# mcp9800.net
KiCad netlist of a schematic drawn in Altium Designer
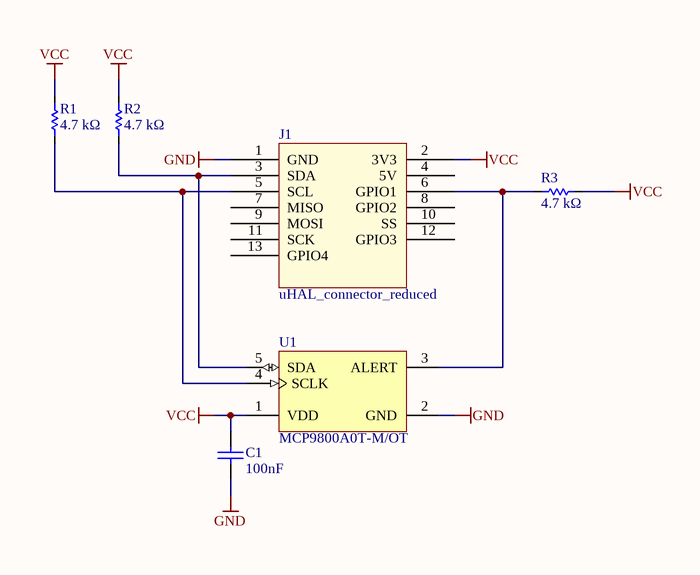
[diagram p0: mcp9800.SchDoc]

(export (version "E")
  (design (tool "Eeschema 10.0.6"))
  (components
    (comp (ref "C1")
      (value "Murata GCM188R71H104KA57D")
      (footprint "CAPC1608X90X35ML10T15")
      (description "CAP CER 0.1UF 50V 10% X7R 0603")
      (fields (field (name "CAPACITANCE") "100nF"))
      (libsource (lib "CommunityVault") (part "CMP-119667-3"))
    )
    (comp (ref "J1")
      (value "uHAL_connector_reduced")
      (footprint "PCB-45ncoppm4oopozvqifsq-1")
      (description "connector for uHAL with reduced pin number")
      (libsource (lib "CommunityVault") (part "CMP-2q23h2cwhjlfm8s6r7i8-1"))
    )
    (comp (ref "R1")
      (value "CRCW06034K70FKEAHP")
      (footprint "PCB-cmzy4aezi5zhn2bew7lt-1")
      (description "Surface Mount Chip Resistor, Thick Film, AEC-Q200 CRCW Series, 4.7 kohm, 250 mW, 1%, 75 V")
      (fields (field (name "RESISTANCE") "4.7 kΩ"))
      (libsource (lib "CommunityVault") (part "CMP-40e08b60e91c9f27-1"))
    )
    (comp (ref "R2")
      (value "CRCW06034K70FKEAHP")
      (footprint "PCB-cmzy4aezi5zhn2bew7lt-1")
      (description "Surface Mount Chip Resistor, Thick Film, AEC-Q200 CRCW Series, 4.7 kohm, 250 mW, 1%, 75 V")
      (fields (field (name "RESISTANCE") "4.7 kΩ"))
      (libsource (lib "CommunityVault") (part "CMP-40e08b60e91c9f27-1"))
    )
    (comp (ref "R3")
      (value "CRCW06034K70FKEAHP")
      (footprint "PCB-cmzy4aezi5zhn2bew7lt-1")
      (description "Surface Mount Chip Resistor, Thick Film, AEC-Q200 CRCW Series, 4.7 kohm, 250 mW, 1%, 75 V")
      (fields (field (name "RESISTANCE") "4.7 kΩ"))
      (libsource (lib "CommunityVault") (part "CMP-40e08b60e91c9f27-1"))
    )
    (comp (ref "U1")
      (value "MCP9800A0T-M/OT")
      (footprint "SOT-23-OT5_L")
      (libsource (lib "CommunityVault") (part "SEN-TEMP-MCP980X-5"))
    )
  )
  (nets
    (net (code "1") (name "GND") (class "Default")
      (node (ref "C1") (pin "1") (pinfunction "1_1") (pintype "passive"))
      (node (ref "J1") (pin "1") (pinfunction "GND_1") (pintype "passive"))
      (node (ref "U1") (pin "2") (pinfunction "GND_2") (pintype "power_in"))
    )
    (net (code "2") (name "Net-(J1-GPIO1)") (class "Default")
      (node (ref "J1") (pin "6") (pinfunction "GPIO1_6") (pintype "passive"))
      (node (ref "R3") (pin "2") (pinfunction "2_2") (pintype "passive"))
      (node (ref "U1") (pin "3") (pinfunction "ALERT_3") (pintype "open_collector"))
    )
    (net (code "3") (name "Net-(J1-SCL)") (class "Default")
      (node (ref "J1") (pin "5") (pinfunction "SCL_5") (pintype "passive"))
      (node (ref "R1") (pin "1") (pinfunction "1_1") (pintype "passive"))
      (node (ref "U1") (pin "4") (pinfunction "SCLK_4") (pintype "input"))
    )
    (net (code "4") (name "Net-(J1-SDA)") (class "Default")
      (node (ref "J1") (pin "3") (pinfunction "SDA_3") (pintype "passive"))
      (node (ref "R2") (pin "1") (pinfunction "1_1") (pintype "passive"))
      (node (ref "U1") (pin "5") (pinfunction "SDA_5") (pintype "bidirectional"))
    )
    (net (code "5") (name "VCC") (class "Default")
      (node (ref "C1") (pin "2") (pinfunction "2_2") (pintype "passive"))
      (node (ref "J1") (pin "2") (pinfunction "3V3_2") (pintype "passive"))
      (node (ref "R1") (pin "2") (pinfunction "2_2") (pintype "passive"))
      (node (ref "R2") (pin "2") (pinfunction "2_2") (pintype "passive"))
      (node (ref "R3") (pin "1") (pinfunction "1_1") (pintype "passive"))
      (node (ref "U1") (pin "1") (pinfunction "VDD_1") (pintype "power_in"))
    )
    (net (code "6") (name "unconnected-(J1-5V-Pad4)") (class "Default")
      (node (ref "J1") (pin "4") (pinfunction "5V_4") (pintype "passive"))
    )
    (net (code "7") (name "unconnected-(J1-GPIO2-Pad8)") (class "Default")
      (node (ref "J1") (pin "8") (pinfunction "GPIO2_8") (pintype "passive"))
    )
    (net (code "8") (name "unconnected-(J1-GPIO3-Pad12)") (class "Default")
      (node (ref "J1") (pin "12") (pinfunction "GPIO3_12") (pintype "passive"))
    )
    (net (code "9") (name "unconnected-(J1-GPIO4-Pad13)") (class "Default")
      (node (ref "J1") (pin "13") (pinfunction "GPIO4_13") (pintype "passive"))
    )
    (net (code "10") (name "unconnected-(J1-MISO-Pad7)") (class "Default")
      (node (ref "J1") (pin "7") (pinfunction "MISO_7") (pintype "passive"))
    )
    (net (code "11") (name "unconnected-(J1-MOSI-Pad9)") (class "Default")
      (node (ref "J1") (pin "9") (pinfunction "MOSI_9") (pintype "passive"))
    )
    (net (code "12") (name "unconnected-(J1-SCK-Pad11)") (class "Default")
      (node (ref "J1") (pin "11") (pinfunction "SCK_11") (pintype "passive"))
    )
    (net (code "13") (name "unconnected-(J1-SS-Pad10)") (class "Default")
      (node (ref "J1") (pin "10") (pinfunction "SS_10") (pintype "passive"))
    )
  )
)
